# Extruder_Fin_System.net
KiCad netlist of a schematic drawn in Altium Designer
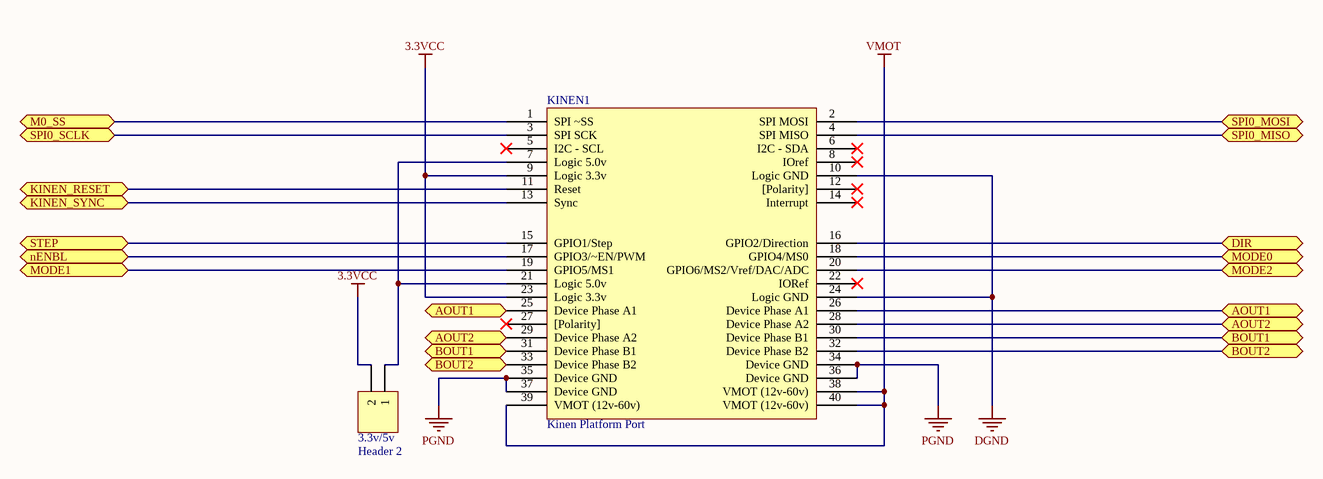
[diagram p0: Extruder Fin System.SchDoc]

(export (version "E")
  (design (tool "Eeschema 10.0.6"))
  (components
    (comp (ref "3.3v/5v")
      (value "Header 2")
      (footprint "HDR1X2")
      (description "Header, 2-Pin")
      (fields (field (name "PUBLISHER") "Altium Limited"))
      (libsource (lib "Miscellaneous Connectors") (part "Header 2"))
    )
    (comp (ref "KINEN1")
      (value "Kinen Platform Port")
      (footprint "Kinen Port")
      (libsource (lib "ExtruderFinLib") (part "Kinen Port"))
    )
  )
  (nets
    (net (code "1") (name "/AOUT1") (class "Default")
      (node (ref "KINEN1") (pin "25") (pinfunction "Device_Phase_A1_25") (pintype "passive"))
      (node (ref "KINEN1") (pin "26") (pinfunction "Device_Phase_A1_26") (pintype "passive"))
    )
    (net (code "2") (name "/AOUT2") (class "Default")
      (node (ref "KINEN1") (pin "28") (pinfunction "Device_Phase_A2_28") (pintype "passive"))
      (node (ref "KINEN1") (pin "29") (pinfunction "Device_Phase_A2_29") (pintype "passive"))
    )
    (net (code "3") (name "/BOUT1") (class "Default")
      (node (ref "KINEN1") (pin "30") (pinfunction "Device_Phase_B1_30") (pintype "passive"))
      (node (ref "KINEN1") (pin "31") (pinfunction "Device_Phase_B1_31") (pintype "passive"))
    )
    (net (code "4") (name "/BOUT2") (class "Default")
      (node (ref "KINEN1") (pin "32") (pinfunction "Device_Phase_B2_32") (pintype "passive"))
      (node (ref "KINEN1") (pin "33") (pinfunction "Device_Phase_B2_33") (pintype "passive"))
    )
    (net (code "5") (name "/DIR") (class "Default")
      (node (ref "KINEN1") (pin "16") (pinfunction "GPIO2/Direction_16") (pintype "passive"))
    )
    (net (code "6") (name "/KINEN_RESET") (class "Default")
      (node (ref "KINEN1") (pin "11") (pinfunction "Reset_11") (pintype "passive"))
    )
    (net (code "7") (name "/KINEN_SYNC") (class "Default")
      (node (ref "KINEN1") (pin "13") (pinfunction "Sync_13") (pintype "passive"))
    )
    (net (code "8") (name "/M0_SS") (class "Default")
      (node (ref "KINEN1") (pin "1") (pinfunction "SPI_~SS_1") (pintype "passive"))
    )
    (net (code "9") (name "/MODE0") (class "Default")
      (node (ref "KINEN1") (pin "18") (pinfunction "GPIO4/MS0_18") (pintype "passive"))
    )
    (net (code "10") (name "/MODE1") (class "Default")
      (node (ref "KINEN1") (pin "19") (pinfunction "GPIO5/MS1_19") (pintype "passive"))
    )
    (net (code "11") (name "/MODE2") (class "Default")
      (node (ref "KINEN1") (pin "20") (pinfunction "GPIO6/MS2/Vref/DAC/ADC_20") (pintype "passive"))
    )
    (net (code "12") (name "/SPI0_MISO") (class "Default")
      (node (ref "KINEN1") (pin "4") (pinfunction "SPI_MISO_4") (pintype "passive"))
    )
    (net (code "13") (name "/SPI0_MOSI") (class "Default")
      (node (ref "KINEN1") (pin "2") (pinfunction "SPI_MOSI_2") (pintype "passive"))
    )
    (net (code "14") (name "/SPI0_SCLK") (class "Default")
      (node (ref "KINEN1") (pin "3") (pinfunction "SPI_SCK_3") (pintype "passive"))
    )
    (net (code "15") (name "/STEP") (class "Default")
      (node (ref "KINEN1") (pin "15") (pinfunction "GPIO1/Step_15") (pintype "passive"))
    )
    (net (code "16") (name "/nENBL") (class "Default")
      (node (ref "KINEN1") (pin "17") (pinfunction "GPIO3/~EN/PWM_17") (pintype "passive"))
    )
    (net (code "17") (name "3.3VCC") (class "Default")
      (node (ref "3.3v/5v") (pin "2") (pinfunction "2_2") (pintype "passive"))
      (node (ref "KINEN1") (pin "23") (pinfunction "Logic_3.3v_23") (pintype "passive"))
      (node (ref "KINEN1") (pin "9") (pinfunction "Logic_3.3v_9") (pintype "passive"))
    )
    (net (code "18") (name "DGND") (class "Default")
      (node (ref "KINEN1") (pin "10") (pinfunction "Logic_GND_10") (pintype "passive"))
      (node (ref "KINEN1") (pin "24") (pinfunction "Logic_GND_24") (pintype "passive"))
    )
    (net (code "19") (name "Net-(3.3v/5v-Pad1)") (class "Default")
      (node (ref "3.3v/5v") (pin "1") (pinfunction "1_1") (pintype "passive"))
      (node (ref "KINEN1") (pin "21") (pinfunction "Logic_5.0v_21") (pintype "passive"))
      (node (ref "KINEN1") (pin "7") (pinfunction "Logic_5.0v_7") (pintype "passive"))
    )
    (net (code "20") (name "PGND") (class "Default")
      (node (ref "KINEN1") (pin "34") (pinfunction "Device_GND_34") (pintype "passive"))
      (node (ref "KINEN1") (pin "35") (pinfunction "Device_GND_35") (pintype "passive"))
      (node (ref "KINEN1") (pin "36") (pinfunction "Device_GND_36") (pintype "passive"))
      (node (ref "KINEN1") (pin "37") (pinfunction "Device_GND_37") (pintype "passive"))
    )
    (net (code "21") (name "VMOT") (class "Default")
      (node (ref "KINEN1") (pin "38") (pinfunction "VMOT_(12v-60v)_38") (pintype "passive"))
      (node (ref "KINEN1") (pin "39") (pinfunction "VMOT_(12v-60v)_39") (pintype "passive"))
      (node (ref "KINEN1") (pin "40") (pinfunction "VMOT_(12v-60v)_40") (pintype "passive"))
    )
    (net (code "22") (name "unconnected-(KINEN1-I2C_-_SCL-Pad5)") (class "Default")
      (node (ref "KINEN1") (pin "5") (pinfunction "I2C_-_SCL_5") (pintype "passive+no_connect"))
    )
    (net (code "23") (name "unconnected-(KINEN1-I2C_-_SDA-Pad6)") (class "Default")
      (node (ref "KINEN1") (pin "6") (pinfunction "I2C_-_SDA_6") (pintype "passive+no_connect"))
    )
    (net (code "24") (name "unconnected-(KINEN1-IORef-Pad22)") (class "Default")
      (node (ref "KINEN1") (pin "22") (pinfunction "IORef_22") (pintype "passive+no_connect"))
    )
    (net (code "25") (name "unconnected-(KINEN1-IOref-Pad8)") (class "Default")
      (node (ref "KINEN1") (pin "8") (pinfunction "IOref_8") (pintype "passive+no_connect"))
    )
    (net (code "26") (name "unconnected-(KINEN1-Interrupt-Pad14)") (class "Default")
      (node (ref "KINEN1") (pin "14") (pinfunction "Interrupt_14") (pintype "passive+no_connect"))
    )
    (net (code "27") (name "unconnected-(KINEN1-[Polarity]-Pad12)") (class "Default")
      (node (ref "KINEN1") (pin "12") (pinfunction "[Polarity]_12") (pintype "passive+no_connect"))
    )
    (net (code "28") (name "unconnected-(KINEN1-[Polarity]-Pad27)") (class "Default")
      (node (ref "KINEN1") (pin "27") (pinfunction "[Polarity]_27") (pintype "passive+no_connect"))
    )
  )
)
